# solenoid-driver.net
KiCad netlist of a schematic drawn in EAGLE
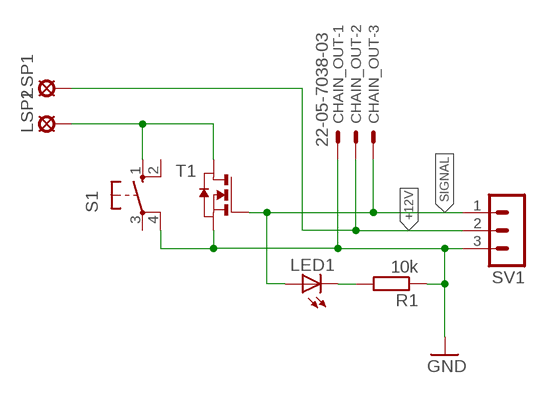
[diagram p0: schematic, sheet 1]

(export (version "E")
  (design (tool "Eeschema 10.0.6"))
  (components
    (comp (ref "CHAIN_OUT")
      (value "22-05-7038-03")
      (footprint "eagle-import:7395-03")
      (fields (field (name "TME") " FCI 76382-303LF "))
      (libsource (lib "eagle-import") (part "22-?-0305-7038"))
    )
    (comp (ref "LED1")
      (value "LEDCHIPLED_1206")
      (footprint "eagle-import:CHIPLED_1206")
      (libsource (lib "eagle-import") (part "LEDCHIPLED_1206"))
    )
    (comp (ref "LSP1")
      (value "LSP13")
      (footprint "eagle-import:LSP13")
      (libsource (lib "eagle-import") (part "LSP13"))
    )
    (comp (ref "LSP2")
      (value "LSP13")
      (footprint "eagle-import:LSP13")
      (libsource (lib "eagle-import") (part "LSP13"))
    )
    (comp (ref "R1")
      (value "10k")
      (footprint "eagle-import:M0805")
      (libsource (lib "eagle-import") (part "R-EU_M0805"))
    )
    (comp (ref "S1")
      (value "10-XX")
      (footprint "eagle-import:B3F-10XX")
      (fields (field (name "MPN") "B3F-1000"))
      (libsource (lib "eagle-import") (part "10-XX"))
    )
    (comp (ref "SV1")
      (value "MA03-1")
      (footprint "eagle-import:MA03-1")
      (libsource (lib "eagle-import") (part "MA03-1"))
    )
    (comp (ref "T1")
      (value "NMOSSOT23")
      (footprint "eagle-import:SOT-23")
      (libsource (lib "eagle-import") (part "NMOSSOT23"))
    )
  )
  (nets
    (net (code "1") (name "+12V") (class "Default")
      (node (ref "CHAIN_OUT") (pin "2") (pinfunction "S_2") (pintype "passive"))
      (node (ref "LSP1") (pin "MP") (pinfunction "MP_MP") (pintype "passive"))
      (node (ref "SV1") (pin "2") (pinfunction "2_2") (pintype "passive"))
    )
    (net (code "2") (name "GND") (class "Default")
      (node (ref "CHAIN_OUT") (pin "1") (pinfunction "S_1") (pintype "passive"))
      (node (ref "R1") (pin "1") (pinfunction "1_1") (pintype "passive"))
      (node (ref "S1") (pin "4") (pinfunction "P1_4") (pintype "passive"))
      (node (ref "SV1") (pin "3") (pinfunction "3_3") (pintype "passive"))
      (node (ref "T1") (pin "2") (pinfunction "S_2") (pintype "passive"))
    )
    (net (code "3") (name "Net-(LED1-PadC)") (class "Default")
      (node (ref "LED1") (pin "C") (pinfunction "C_C") (pintype "passive"))
      (node (ref "R1") (pin "2") (pinfunction "2_2") (pintype "passive"))
    )
    (net (code "4") (name "Net-(S1-S)") (class "Default")
      (node (ref "LSP2") (pin "MP") (pinfunction "MP_MP") (pintype "passive"))
      (node (ref "S1") (pin "1") (pinfunction "S_1") (pintype "passive"))
      (node (ref "T1") (pin "1") (pinfunction "D_1") (pintype "passive"))
    )
    (net (code "5") (name "SIGNAL") (class "Default")
      (node (ref "CHAIN_OUT") (pin "3") (pinfunction "S_3") (pintype "passive"))
      (node (ref "LED1") (pin "A") (pinfunction "A_A") (pintype "passive"))
      (node (ref "SV1") (pin "1") (pinfunction "1_1") (pintype "passive"))
      (node (ref "T1") (pin "3") (pinfunction "G_3") (pintype "passive"))
    )
    (net (code "6") (name "unconnected-(S1-P-Pad3)") (class "Default")
      (node (ref "S1") (pin "3") (pinfunction "P_3") (pintype "passive"))
    )
    (net (code "7") (name "unconnected-(S1-S1-Pad2)") (class "Default")
      (node (ref "S1") (pin "2") (pinfunction "S1_2") (pintype "passive"))
    )
  )
)
